# PowerBoard.net
KiCad netlist of a schematic drawn in Altium Designer
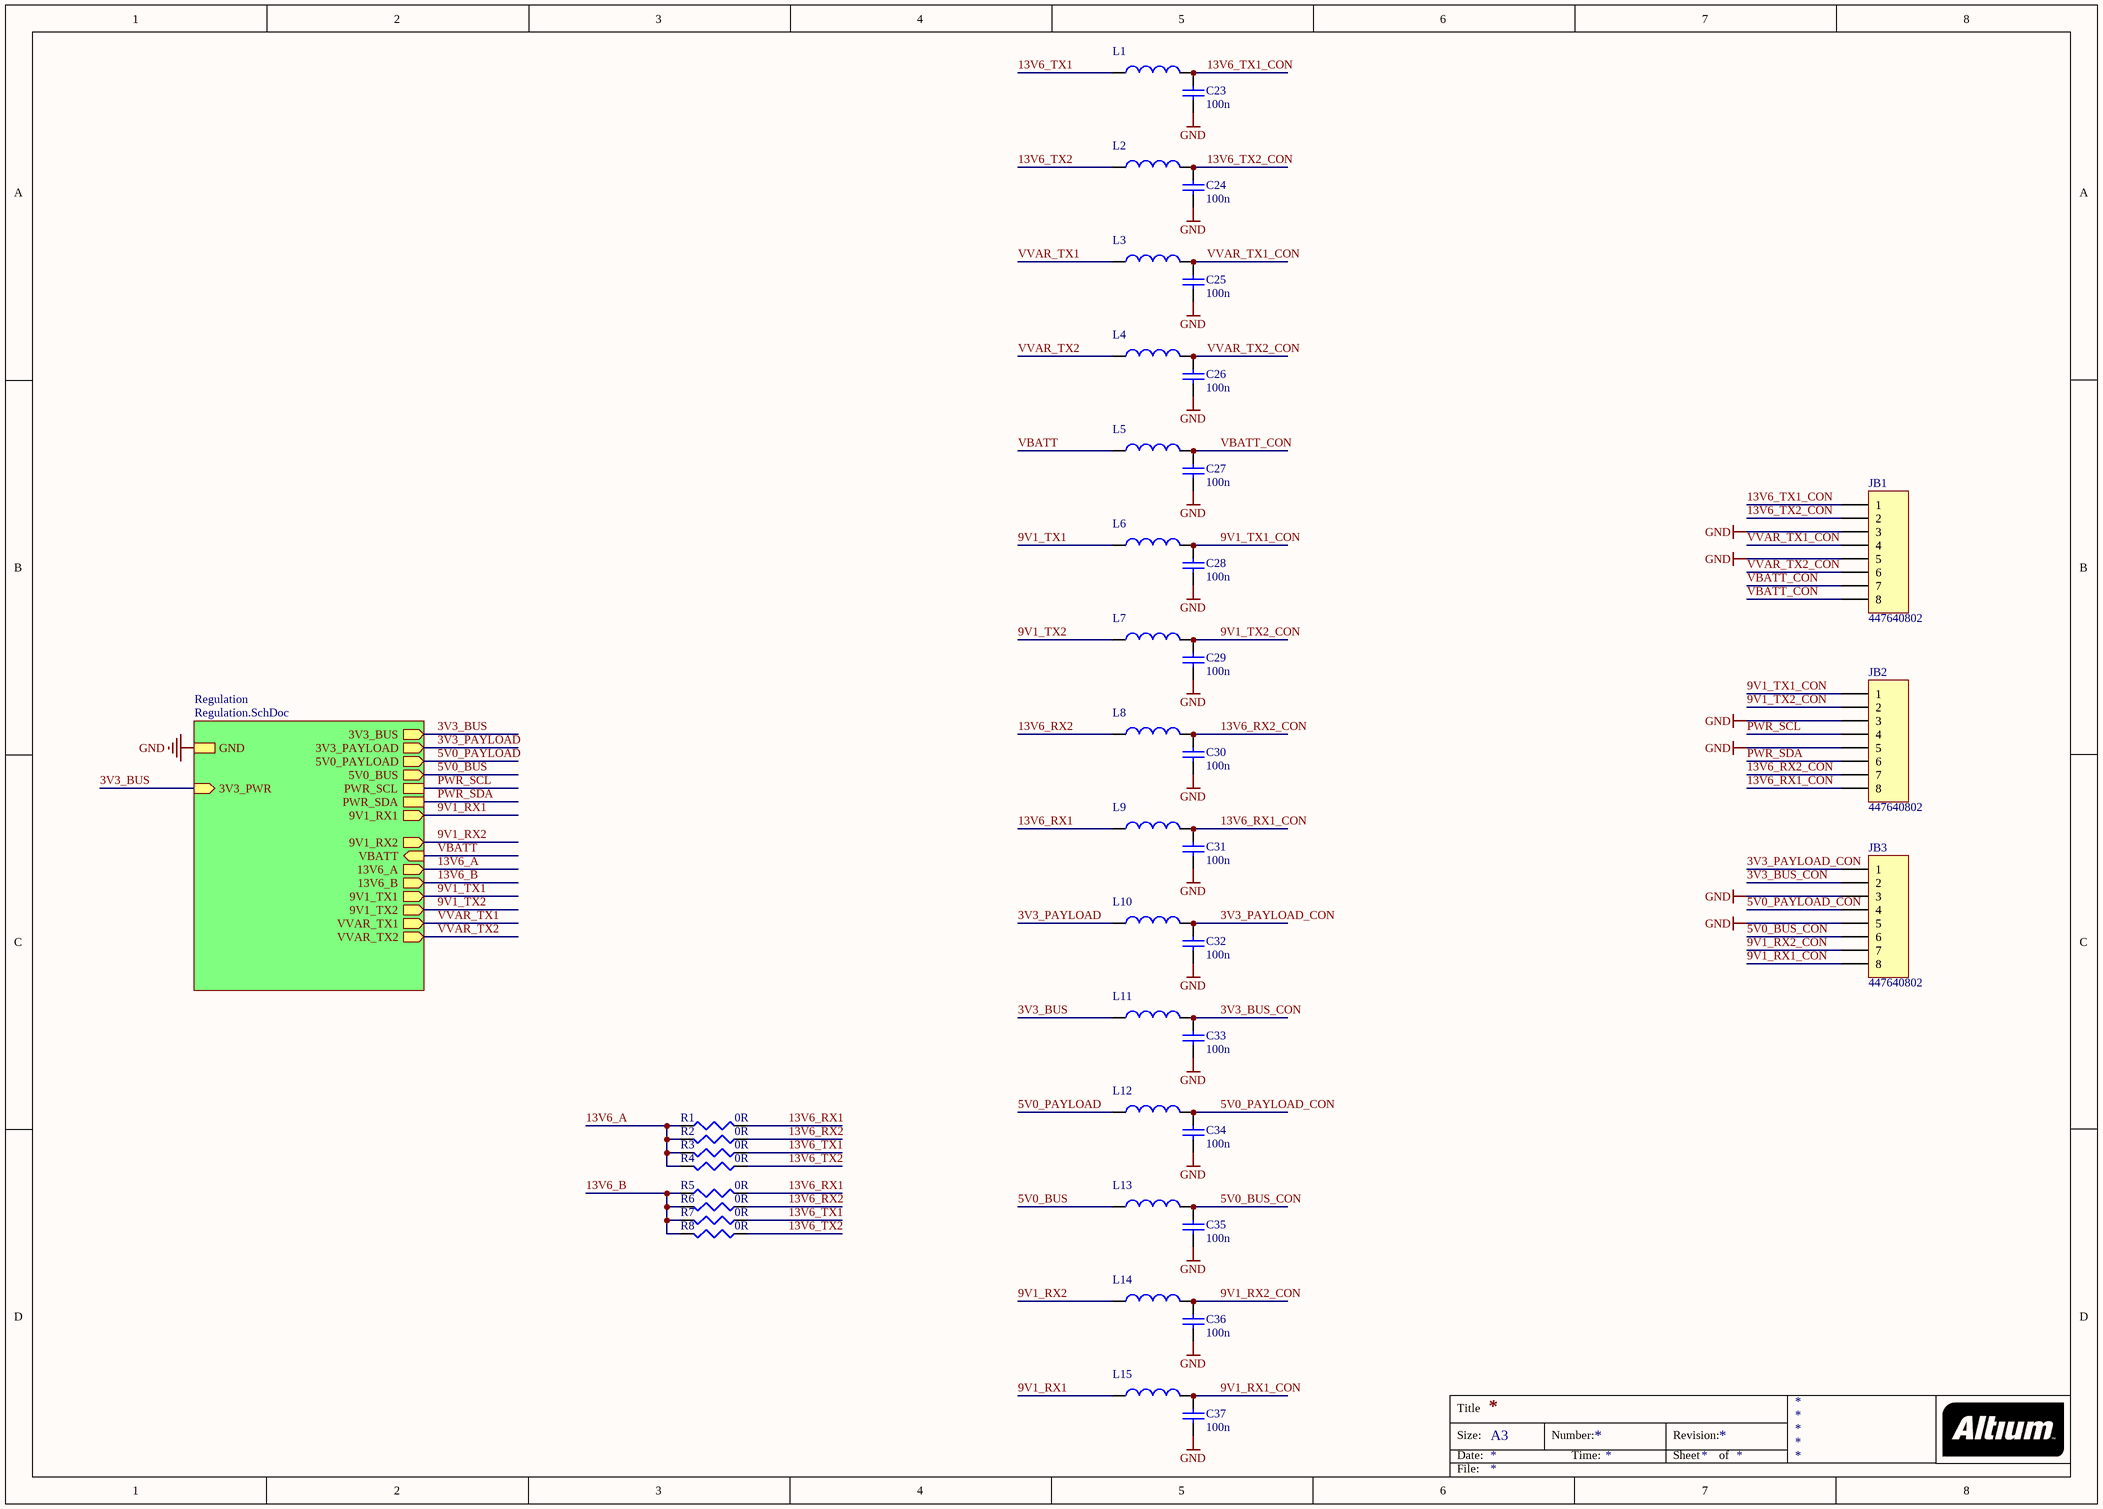
[diagram p0: PowerBoard.SchDoc]

(export (version "E")
  (design (tool "Eeschema 10.0.6"))
  (components
    (comp (ref "C23")
      (value "100n")
      (footprint "R0805M")
      (description "Capacitor")
      (fields (field (name "PUBLISHER") "Altium Limited"))
      (libsource (lib "Miscellaneous Devices") (part "Cap"))
    )
    (comp (ref "C24")
      (value "100n")
      (footprint "R0805M")
      (description "Capacitor")
      (fields (field (name "PUBLISHER") "Altium Limited"))
      (libsource (lib "Miscellaneous Devices") (part "Cap"))
    )
    (comp (ref "C25")
      (value "100n")
      (footprint "R0805M")
      (description "Capacitor")
      (fields (field (name "PUBLISHER") "Altium Limited"))
      (libsource (lib "Miscellaneous Devices") (part "Cap"))
    )
    (comp (ref "C26")
      (value "100n")
      (footprint "R0805M")
      (description "Capacitor")
      (fields (field (name "PUBLISHER") "Altium Limited"))
      (libsource (lib "Miscellaneous Devices") (part "Cap"))
    )
    (comp (ref "C27")
      (value "100n")
      (footprint "R0805M")
      (description "Capacitor")
      (fields (field (name "PUBLISHER") "Altium Limited"))
      (libsource (lib "Miscellaneous Devices") (part "Cap"))
    )
    (comp (ref "C28")
      (value "100n")
      (footprint "R0805M")
      (description "Capacitor")
      (fields (field (name "PUBLISHER") "Altium Limited"))
      (libsource (lib "Miscellaneous Devices") (part "Cap"))
    )
    (comp (ref "C29")
      (value "100n")
      (footprint "R0805M")
      (description "Capacitor")
      (fields (field (name "PUBLISHER") "Altium Limited"))
      (libsource (lib "Miscellaneous Devices") (part "Cap"))
    )
    (comp (ref "C30")
      (value "100n")
      (footprint "R0805M")
      (description "Capacitor")
      (fields (field (name "PUBLISHER") "Altium Limited"))
      (libsource (lib "Miscellaneous Devices") (part "Cap"))
    )
    (comp (ref "C31")
      (value "100n")
      (footprint "R0805M")
      (description "Capacitor")
      (fields (field (name "PUBLISHER") "Altium Limited"))
      (libsource (lib "Miscellaneous Devices") (part "Cap"))
    )
    (comp (ref "C32")
      (value "100n")
      (footprint "R0805M")
      (description "Capacitor")
      (fields (field (name "PUBLISHER") "Altium Limited"))
      (libsource (lib "Miscellaneous Devices") (part "Cap"))
    )
    (comp (ref "C33")
      (value "100n")
      (footprint "R0805M")
      (description "Capacitor")
      (fields (field (name "PUBLISHER") "Altium Limited"))
      (libsource (lib "Miscellaneous Devices") (part "Cap"))
    )
    (comp (ref "C34")
      (value "100n")
      (footprint "R0805M")
      (description "Capacitor")
      (fields (field (name "PUBLISHER") "Altium Limited"))
      (libsource (lib "Miscellaneous Devices") (part "Cap"))
    )
    (comp (ref "C35")
      (value "100n")
      (footprint "R0805M")
      (description "Capacitor")
      (fields (field (name "PUBLISHER") "Altium Limited"))
      (libsource (lib "Miscellaneous Devices") (part "Cap"))
    )
    (comp (ref "C36")
      (value "100n")
      (footprint "R0805M")
      (description "Capacitor")
      (fields (field (name "PUBLISHER") "Altium Limited"))
      (libsource (lib "Miscellaneous Devices") (part "Cap"))
    )
    (comp (ref "C37")
      (value "100n")
      (footprint "R0805M")
      (description "Capacitor")
      (fields (field (name "PUBLISHER") "Altium Limited"))
      (libsource (lib "Miscellaneous Devices") (part "Cap"))
    )
    (comp (ref "JB1")
      (value "447640802")
      (footprint "MOLEX 447640802")
      (description "B2B RA Receptacle")
      (libsource (lib "SchLib") (part "MOLEX 447640802"))
    )
    (comp (ref "JB2")
      (value "447640802")
      (footprint "MOLEX 447640802")
      (description "B2B RA Receptacle")
      (libsource (lib "SchLib") (part "MOLEX 447640802"))
    )
    (comp (ref "JB3")
      (value "447640802")
      (footprint "MOLEX 447640802")
      (description "B2B RA Receptacle")
      (libsource (lib "SchLib") (part "MOLEX 447640802"))
    )
    (comp (ref "L1")
      (value "BLM31PG121SN1L")
      (footprint "INDC3216M")
      (description "Ferrite Bead")
      (fields (field (name "PUBLISHER") "Altium Limited"))
      (libsource (lib "SchLib") (part "Inductor"))
    )
    (comp (ref "L2")
      (value "BLM31PG121SN1L")
      (footprint "INDC3216M")
      (description "Ferrite Bead")
      (fields (field (name "PUBLISHER") "Altium Limited"))
      (libsource (lib "SchLib") (part "Inductor"))
    )
    (comp (ref "L3")
      (value "BLM31PG121SN1L")
      (footprint "INDC3216M")
      (description "Ferrite Bead")
      (fields (field (name "PUBLISHER") "Altium Limited"))
      (libsource (lib "SchLib") (part "Inductor"))
    )
    (comp (ref "L4")
      (value "BLM31PG121SN1L")
      (footprint "INDC3216M")
      (description "Ferrite Bead")
      (fields (field (name "PUBLISHER") "Altium Limited"))
      (libsource (lib "SchLib") (part "Inductor"))
    )
    (comp (ref "L5")
      (value "BLM31PG121SN1L")
      (footprint "INDC3216M")
      (description "Ferrite Bead")
      (fields (field (name "PUBLISHER") "Altium Limited"))
      (libsource (lib "SchLib") (part "Inductor"))
    )
    (comp (ref "L6")
      (value "BLM31PG121SN1L")
      (footprint "INDC3216M")
      (description "Ferrite Bead")
      (fields (field (name "PUBLISHER") "Altium Limited"))
      (libsource (lib "SchLib") (part "Inductor"))
    )
    (comp (ref "L7")
      (value "BLM31PG121SN1L")
      (footprint "INDC3216M")
      (description "Ferrite Bead")
      (fields (field (name "PUBLISHER") "Altium Limited"))
      (libsource (lib "SchLib") (part "Inductor"))
    )
    (comp (ref "L8")
      (value "BLM31PG121SN1L")
      (footprint "INDC3216M")
      (description "Ferrite Bead")
      (fields (field (name "PUBLISHER") "Altium Limited"))
      (libsource (lib "SchLib") (part "Inductor"))
    )
    (comp (ref "L9")
      (value "BLM31PG121SN1L")
      (footprint "INDC3216M")
      (description "Ferrite Bead")
      (fields (field (name "PUBLISHER") "Altium Limited"))
      (libsource (lib "SchLib") (part "Inductor"))
    )
    (comp (ref "L10")
      (value "BLM31PG121SN1L")
      (footprint "INDC3216M")
      (description "Ferrite Bead")
      (fields (field (name "PUBLISHER") "Altium Limited"))
      (libsource (lib "SchLib") (part "Inductor"))
    )
    (comp (ref "L11")
      (value "BLM31PG121SN1L")
      (footprint "INDC3216M")
      (description "Ferrite Bead")
      (fields (field (name "PUBLISHER") "Altium Limited"))
      (libsource (lib "SchLib") (part "Inductor"))
    )
    (comp (ref "L12")
      (value "BLM31PG121SN1L")
      (footprint "INDC3216M")
      (description "Ferrite Bead")
      (fields (field (name "PUBLISHER") "Altium Limited"))
      (libsource (lib "SchLib") (part "Inductor"))
    )
    (comp (ref "L13")
      (value "BLM31PG121SN1L")
      (footprint "INDC3216M")
      (description "Ferrite Bead")
      (fields (field (name "PUBLISHER") "Altium Limited"))
      (libsource (lib "SchLib") (part "Inductor"))
    )
    (comp (ref "L14")
      (value "BLM31PG121SN1L")
      (footprint "INDC3216M")
      (description "Ferrite Bead")
      (fields (field (name "PUBLISHER") "Altium Limited"))
      (libsource (lib "SchLib") (part "Inductor"))
    )
    (comp (ref "L15")
      (value "BLM31PG121SN1L")
      (footprint "INDC3216M")
      (description "Ferrite Bead")
      (fields (field (name "PUBLISHER") "Altium Limited"))
      (libsource (lib "SchLib") (part "Inductor"))
    )
    (comp (ref "R1")
      (value "0R")
      (footprint "R0402M")
      (description "Resistor")
      (fields (field (name "PUBLISHER") "Altium Limited"))
      (libsource (lib "Miscellaneous Devices") (part "Res3"))
    )
    (comp (ref "R2")
      (value "0R")
      (footprint "R0402M")
      (description "Resistor")
      (fields (field (name "PUBLISHER") "Altium Limited"))
      (libsource (lib "Miscellaneous Devices") (part "Res3"))
    )
    (comp (ref "R3")
      (value "0R")
      (footprint "R0402M")
      (description "Resistor")
      (fields (field (name "PUBLISHER") "Altium Limited"))
      (libsource (lib "Miscellaneous Devices") (part "Res3"))
    )
    (comp (ref "R4")
      (value "0R")
      (footprint "R0402M")
      (description "Resistor")
      (fields (field (name "PUBLISHER") "Altium Limited"))
      (libsource (lib "Miscellaneous Devices") (part "Res3"))
    )
    (comp (ref "R5")
      (value "0R")
      (footprint "R0402M")
      (description "Resistor")
      (fields (field (name "PUBLISHER") "Altium Limited"))
      (libsource (lib "Miscellaneous Devices") (part "Res3"))
    )
    (comp (ref "R6")
      (value "0R")
      (footprint "R0402M")
      (description "Resistor")
      (fields (field (name "PUBLISHER") "Altium Limited"))
      (libsource (lib "Miscellaneous Devices") (part "Res3"))
    )
    (comp (ref "R7")
      (value "0R")
      (footprint "R0402M")
      (description "Resistor")
      (fields (field (name "PUBLISHER") "Altium Limited"))
      (libsource (lib "Miscellaneous Devices") (part "Res3"))
    )
    (comp (ref "R8")
      (value "0R")
      (footprint "R0402M")
      (description "Resistor")
      (fields (field (name "PUBLISHER") "Altium Limited"))
      (libsource (lib "Miscellaneous Devices") (part "Res3"))
    )
  )
  (nets
    (net (code "1") (name "/3V3_BUS") (class "Default")
      (node (ref "L11") (pin "1") (pinfunction "1_1") (pintype "passive"))
    )
    (net (code "2") (name "/3V3_BUS_CON") (class "Default")
      (node (ref "C33") (pin "1") (pinfunction "1_1") (pintype "passive"))
      (node (ref "JB3") (pin "2") (pinfunction "2_2") (pintype "passive"))
      (node (ref "L11") (pin "2") (pinfunction "2_2") (pintype "passive"))
    )
    (net (code "3") (name "/3V3_PAYLOAD") (class "Default")
      (node (ref "L10") (pin "1") (pinfunction "1_1") (pintype "passive"))
    )
    (net (code "4") (name "/3V3_PAYLOAD_CON") (class "Default")
      (node (ref "C32") (pin "1") (pinfunction "1_1") (pintype "passive"))
      (node (ref "JB3") (pin "1") (pinfunction "1_1") (pintype "passive"))
      (node (ref "L10") (pin "2") (pinfunction "2_2") (pintype "passive"))
    )
    (net (code "5") (name "/5V0_BUS") (class "Default")
      (node (ref "L13") (pin "1") (pinfunction "1_1") (pintype "passive"))
    )
    (net (code "6") (name "/5V0_BUS_CON") (class "Default")
      (node (ref "C35") (pin "1") (pinfunction "1_1") (pintype "passive"))
      (node (ref "JB3") (pin "6") (pinfunction "6_6") (pintype "passive"))
      (node (ref "L13") (pin "2") (pinfunction "2_2") (pintype "passive"))
    )
    (net (code "7") (name "/5V0_PAYLOAD") (class "Default")
      (node (ref "L12") (pin "1") (pinfunction "1_1") (pintype "passive"))
    )
    (net (code "8") (name "/5V0_PAYLOAD_CON") (class "Default")
      (node (ref "C34") (pin "1") (pinfunction "1_1") (pintype "passive"))
      (node (ref "JB3") (pin "4") (pinfunction "4_4") (pintype "passive"))
      (node (ref "L12") (pin "2") (pinfunction "2_2") (pintype "passive"))
    )
    (net (code "9") (name "/9V1_RX1") (class "Default")
      (node (ref "L15") (pin "1") (pinfunction "1_1") (pintype "passive"))
    )
    (net (code "10") (name "/9V1_RX1_CON") (class "Default")
      (node (ref "C37") (pin "1") (pinfunction "1_1") (pintype "passive"))
      (node (ref "JB3") (pin "8") (pinfunction "8_8") (pintype "passive"))
      (node (ref "L15") (pin "2") (pinfunction "2_2") (pintype "passive"))
    )
    (net (code "11") (name "/9V1_RX2") (class "Default")
      (node (ref "L14") (pin "1") (pinfunction "1_1") (pintype "passive"))
    )
    (net (code "12") (name "/9V1_RX2_CON") (class "Default")
      (node (ref "C36") (pin "1") (pinfunction "1_1") (pintype "passive"))
      (node (ref "JB3") (pin "7") (pinfunction "7_7") (pintype "passive"))
      (node (ref "L14") (pin "2") (pinfunction "2_2") (pintype "passive"))
    )
    (net (code "13") (name "/9V1_TX1") (class "Default")
      (node (ref "L6") (pin "1") (pinfunction "1_1") (pintype "passive"))
    )
    (net (code "14") (name "/9V1_TX1_CON") (class "Default")
      (node (ref "C28") (pin "1") (pinfunction "1_1") (pintype "passive"))
      (node (ref "JB2") (pin "1") (pinfunction "1_1") (pintype "passive"))
      (node (ref "L6") (pin "2") (pinfunction "2_2") (pintype "passive"))
    )
    (net (code "15") (name "/9V1_TX2") (class "Default")
      (node (ref "L7") (pin "1") (pinfunction "1_1") (pintype "passive"))
    )
    (net (code "16") (name "/9V1_TX2_CON") (class "Default")
      (node (ref "C29") (pin "1") (pinfunction "1_1") (pintype "passive"))
      (node (ref "JB2") (pin "2") (pinfunction "2_2") (pintype "passive"))
      (node (ref "L7") (pin "2") (pinfunction "2_2") (pintype "passive"))
    )
    (net (code "17") (name "/13V6_A") (class "Default")
      (node (ref "R1") (pin "1") (pinfunction "1_1") (pintype "passive"))
      (node (ref "R2") (pin "2") (pinfunction "2_2") (pintype "passive"))
      (node (ref "R3") (pin "2") (pinfunction "2_2") (pintype "passive"))
      (node (ref "R4") (pin "2") (pinfunction "2_2") (pintype "passive"))
    )
    (net (code "18") (name "/13V6_B") (class "Default")
      (node (ref "R5") (pin "1") (pinfunction "1_1") (pintype "passive"))
      (node (ref "R6") (pin "2") (pinfunction "2_2") (pintype "passive"))
      (node (ref "R7") (pin "2") (pinfunction "2_2") (pintype "passive"))
      (node (ref "R8") (pin "2") (pinfunction "2_2") (pintype "passive"))
    )
    (net (code "19") (name "/13V6_RX1") (class "Default")
      (node (ref "L9") (pin "1") (pinfunction "1_1") (pintype "passive"))
      (node (ref "R1") (pin "2") (pinfunction "2_2") (pintype "passive"))
      (node (ref "R5") (pin "2") (pinfunction "2_2") (pintype "passive"))
    )
    (net (code "20") (name "/13V6_RX1_CON") (class "Default")
      (node (ref "C31") (pin "1") (pinfunction "1_1") (pintype "passive"))
      (node (ref "JB2") (pin "8") (pinfunction "8_8") (pintype "passive"))
      (node (ref "L9") (pin "2") (pinfunction "2_2") (pintype "passive"))
    )
    (net (code "21") (name "/13V6_RX2") (class "Default")
      (node (ref "L8") (pin "1") (pinfunction "1_1") (pintype "passive"))
      (node (ref "R2") (pin "1") (pinfunction "1_1") (pintype "passive"))
      (node (ref "R6") (pin "1") (pinfunction "1_1") (pintype "passive"))
    )
    (net (code "22") (name "/13V6_RX2_CON") (class "Default")
      (node (ref "C30") (pin "1") (pinfunction "1_1") (pintype "passive"))
      (node (ref "JB2") (pin "7") (pinfunction "7_7") (pintype "passive"))
      (node (ref "L8") (pin "2") (pinfunction "2_2") (pintype "passive"))
    )
    (net (code "23") (name "/13V6_TX1") (class "Default")
      (node (ref "L1") (pin "1") (pinfunction "1_1") (pintype "passive"))
      (node (ref "R3") (pin "1") (pinfunction "1_1") (pintype "passive"))
      (node (ref "R7") (pin "1") (pinfunction "1_1") (pintype "passive"))
    )
    (net (code "24") (name "/13V6_TX1_CON") (class "Default")
      (node (ref "C23") (pin "1") (pinfunction "1_1") (pintype "passive"))
      (node (ref "JB1") (pin "1") (pinfunction "1_1") (pintype "passive"))
      (node (ref "L1") (pin "2") (pinfunction "2_2") (pintype "passive"))
    )
    (net (code "25") (name "/13V6_TX2") (class "Default")
      (node (ref "L2") (pin "1") (pinfunction "1_1") (pintype "passive"))
      (node (ref "R4") (pin "1") (pinfunction "1_1") (pintype "passive"))
      (node (ref "R8") (pin "1") (pinfunction "1_1") (pintype "passive"))
    )
    (net (code "26") (name "/13V6_TX2_CON") (class "Default")
      (node (ref "C24") (pin "1") (pinfunction "1_1") (pintype "passive"))
      (node (ref "JB1") (pin "2") (pinfunction "2_2") (pintype "passive"))
      (node (ref "L2") (pin "2") (pinfunction "2_2") (pintype "passive"))
    )
    (net (code "27") (name "/PWR_SCL") (class "Default")
      (node (ref "JB2") (pin "4") (pinfunction "4_4") (pintype "passive"))
    )
    (net (code "28") (name "/PWR_SDA") (class "Default")
      (node (ref "JB2") (pin "6") (pinfunction "6_6") (pintype "passive"))
    )
    (net (code "29") (name "/VBATT") (class "Default")
      (node (ref "L5") (pin "1") (pinfunction "1_1") (pintype "passive"))
    )
    (net (code "30") (name "/VBATT_CON") (class "Default")
      (node (ref "C27") (pin "1") (pinfunction "1_1") (pintype "passive"))
      (node (ref "JB1") (pin "7") (pinfunction "7_7") (pintype "passive"))
      (node (ref "JB1") (pin "8") (pinfunction "8_8") (pintype "passive"))
      (node (ref "L5") (pin "2") (pinfunction "2_2") (pintype "passive"))
    )
    (net (code "31") (name "/VVAR_TX1") (class "Default")
      (node (ref "L3") (pin "1") (pinfunction "1_1") (pintype "passive"))
    )
    (net (code "32") (name "/VVAR_TX1_CON") (class "Default")
      (node (ref "C25") (pin "1") (pinfunction "1_1") (pintype "passive"))
      (node (ref "JB1") (pin "4") (pinfunction "4_4") (pintype "passive"))
      (node (ref "L3") (pin "2") (pinfunction "2_2") (pintype "passive"))
    )
    (net (code "33") (name "/VVAR_TX2") (class "Default")
      (node (ref "L4") (pin "1") (pinfunction "1_1") (pintype "passive"))
    )
    (net (code "34") (name "/VVAR_TX2_CON") (class "Default")
      (node (ref "C26") (pin "1") (pinfunction "1_1") (pintype "passive"))
      (node (ref "JB1") (pin "6") (pinfunction "6_6") (pintype "passive"))
      (node (ref "L4") (pin "2") (pinfunction "2_2") (pintype "passive"))
    )
    (net (code "35") (name "GND") (class "Default")
      (node (ref "C23") (pin "2") (pinfunction "2_2") (pintype "passive"))
      (node (ref "C24") (pin "2") (pinfunction "2_2") (pintype "passive"))
      (node (ref "C25") (pin "2") (pinfunction "2_2") (pintype "passive"))
      (node (ref "C26") (pin "2") (pinfunction "2_2") (pintype "passive"))
      (node (ref "C27") (pin "2") (pinfunction "2_2") (pintype "passive"))
      (node (ref "C28") (pin "2") (pinfunction "2_2") (pintype "passive"))
      (node (ref "C29") (pin "2") (pinfunction "2_2") (pintype "passive"))
      (node (ref "C30") (pin "2") (pinfunction "2_2") (pintype "passive"))
      (node (ref "C31") (pin "2") (pinfunction "2_2") (pintype "passive"))
      (node (ref "C32") (pin "2") (pinfunction "2_2") (pintype "passive"))
      (node (ref "C33") (pin "2") (pinfunction "2_2") (pintype "passive"))
      (node (ref "C34") (pin "2") (pinfunction "2_2") (pintype "passive"))
      (node (ref "C35") (pin "2") (pinfunction "2_2") (pintype "passive"))
      (node (ref "C36") (pin "2") (pinfunction "2_2") (pintype "passive"))
      (node (ref "C37") (pin "2") (pinfunction "2_2") (pintype "passive"))
      (node (ref "JB1") (pin "3") (pinfunction "3_3") (pintype "passive"))
      (node (ref "JB1") (pin "5") (pinfunction "5_5") (pintype "passive"))
      (node (ref "JB2") (pin "3") (pinfunction "3_3") (pintype "passive"))
      (node (ref "JB2") (pin "5") (pinfunction "5_5") (pintype "passive"))
      (node (ref "JB3") (pin "3") (pinfunction "3_3") (pintype "passive"))
      (node (ref "JB3") (pin "5") (pinfunction "5_5") (pintype "passive"))
    )
  )
)
